# CanBusFinalICSP.net
KiCad netlist of a schematic drawn in EAGLE
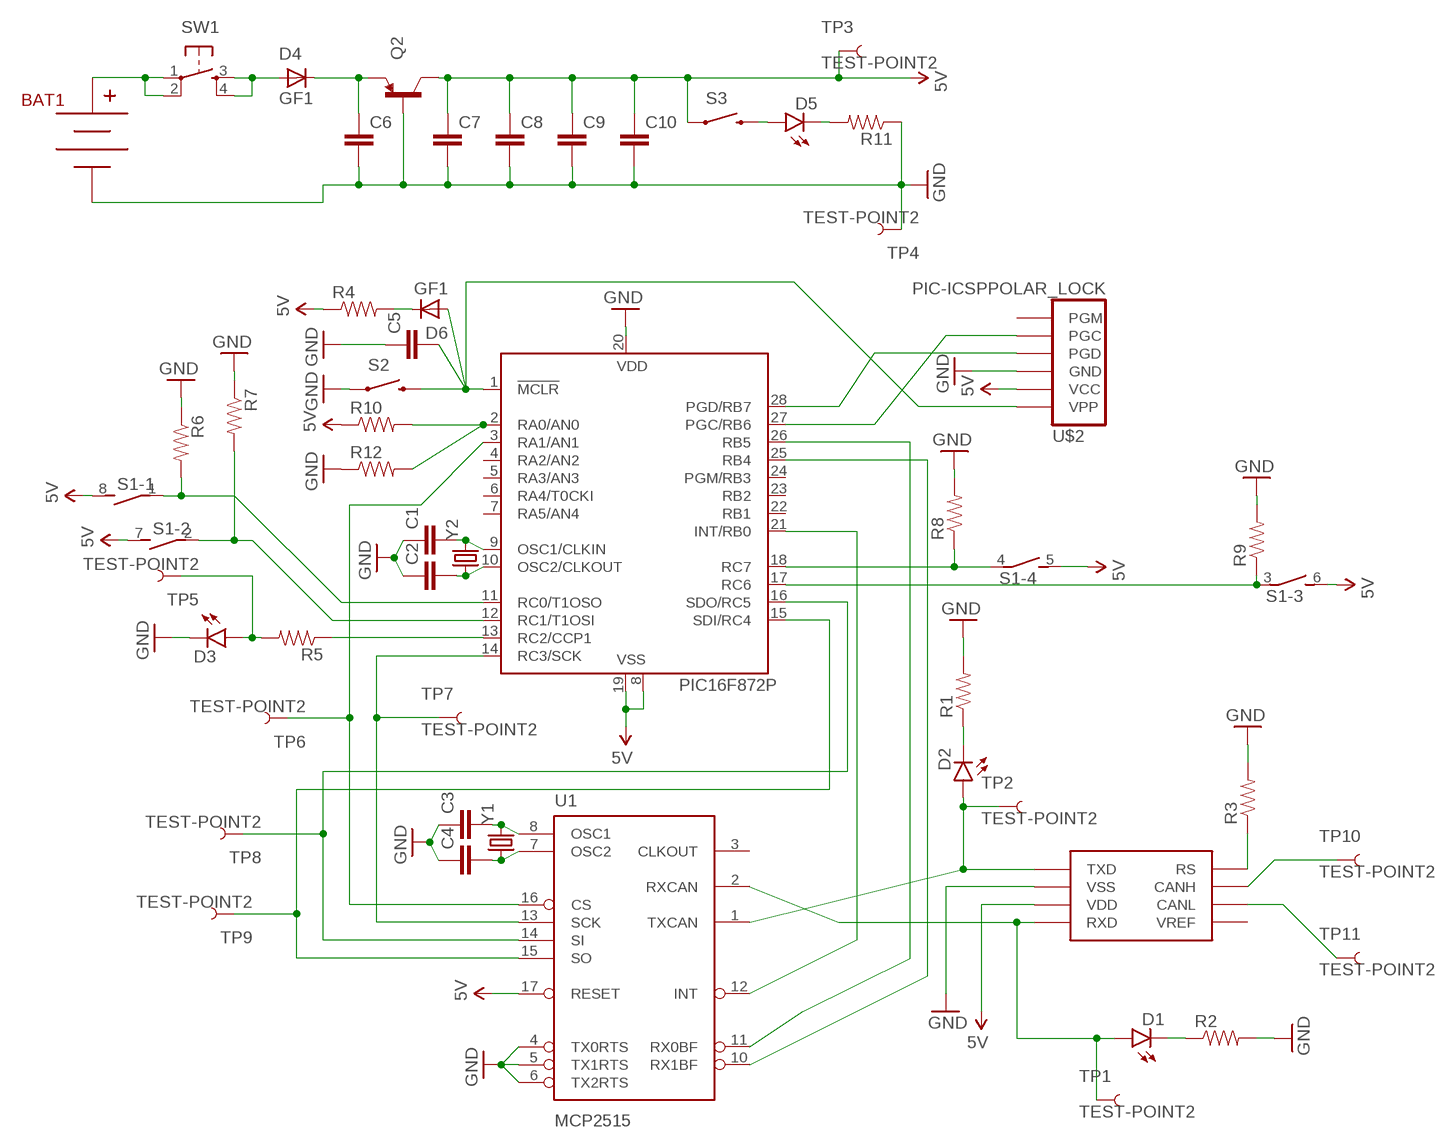
[diagram p0: schematic, sheet 1]

(export (version "E")
  (design (tool "Eeschema 10.0.6"))
  (components
    (comp (ref "BAT1")
      (value "BC9VPC")
      (footprint "eagle-import:BC9VPC")
      (libsource (lib "eagle-import") (part "BC9VPC"))
    )
    (comp (ref "C1")
      (value "CAPPTH")
      (footprint "eagle-import:CAP-PTH-SMALL")
      (libsource (lib "eagle-import") (part "CAPPTH"))
    )
    (comp (ref "C2")
      (value "CAPPTH")
      (footprint "eagle-import:CAP-PTH-SMALL")
      (libsource (lib "eagle-import") (part "CAPPTH"))
    )
    (comp (ref "C3")
      (value "CAPPTH")
      (footprint "eagle-import:CAP-PTH-SMALL")
      (libsource (lib "eagle-import") (part "CAPPTH"))
    )
    (comp (ref "C4")
      (value "CAPPTH")
      (footprint "eagle-import:CAP-PTH-SMALL")
      (libsource (lib "eagle-import") (part "CAPPTH"))
    )
    (comp (ref "C5")
      (value "CAPPTH")
      (footprint "eagle-import:CAP-PTH-SMALL")
      (libsource (lib "eagle-import") (part "CAPPTH"))
    )
    (comp (ref "C6")
      (value "CAPPTH")
      (footprint "eagle-import:CAP-PTH-SMALL")
      (libsource (lib "eagle-import") (part "CAPPTH"))
    )
    (comp (ref "C7")
      (value "CAPPTH")
      (footprint "eagle-import:CAP-PTH-SMALL")
      (libsource (lib "eagle-import") (part "CAPPTH"))
    )
    (comp (ref "C8")
      (value "CAPPTH")
      (footprint "eagle-import:CAP-PTH-SMALL")
      (libsource (lib "eagle-import") (part "CAPPTH"))
    )
    (comp (ref "C9")
      (value "CAPPTH")
      (footprint "eagle-import:CAP-PTH-SMALL")
      (libsource (lib "eagle-import") (part "CAPPTH"))
    )
    (comp (ref "C10")
      (value "CAPPTH")
      (footprint "eagle-import:CAP-PTH-SMALL")
      (libsource (lib "eagle-import") (part "CAPPTH"))
    )
    (comp (ref "D1")
      (value "LED5MM")
      (footprint "eagle-import:LED5MM")
      (libsource (lib "eagle-import") (part "LED5MM"))
    )
    (comp (ref "D2")
      (value "LED5MM")
      (footprint "eagle-import:LED5MM")
      (libsource (lib "eagle-import") (part "LED5MM"))
    )
    (comp (ref "D3")
      (value "LED5MM")
      (footprint "eagle-import:LED5MM")
      (libsource (lib "eagle-import") (part "LED5MM"))
    )
    (comp (ref "D4")
      (value "GF1")
      (footprint "eagle-import:SMA-DO214AC")
      (libsource (lib "eagle-import") (part "GF1"))
    )
    (comp (ref "D5")
      (value "LED5MM")
      (footprint "eagle-import:LED5MM")
      (libsource (lib "eagle-import") (part "LED5MM"))
    )
    (comp (ref "D6")
      (value "GF1")
      (footprint "eagle-import:SMA-DO214AC")
      (libsource (lib "eagle-import") (part "GF1"))
    )
    (comp (ref "IC1")
      (value "PIC16F872P")
      (footprint "eagle-import:DIL28-3")
      (fields (field (name "MF") "MICROCHIP") (field (name "MPN") "PIC16F872-I/SP"))
      (libsource (lib "eagle-import") (part "PIC16872PF"))
    )
    (comp (ref "Q2")
      (value "TRANSISTOR_PNPTO92")
      (footprint "eagle-import:TO-92")
      (libsource (lib "eagle-import") (part "TRANSISTOR_PNPTO92"))
    )
    (comp (ref "R1")
      (value "RESISTOREZ")
      (footprint "eagle-import:AXIAL-0.3EZ")
      (libsource (lib "eagle-import") (part "RESISTOREZ"))
    )
    (comp (ref "R2")
      (value "RESISTOREZ")
      (footprint "eagle-import:AXIAL-0.3EZ")
      (libsource (lib "eagle-import") (part "RESISTOREZ"))
    )
    (comp (ref "R3")
      (value "RESISTOREZ")
      (footprint "eagle-import:AXIAL-0.3EZ")
      (libsource (lib "eagle-import") (part "RESISTOREZ"))
    )
    (comp (ref "R4")
      (value "RESISTOREZ")
      (footprint "eagle-import:AXIAL-0.3EZ")
      (libsource (lib "eagle-import") (part "RESISTOREZ"))
    )
    (comp (ref "R5")
      (value "RESISTOREZ")
      (footprint "eagle-import:AXIAL-0.3EZ")
      (libsource (lib "eagle-import") (part "RESISTOREZ"))
    )
    (comp (ref "R6")
      (value "RESISTOREZ")
      (footprint "eagle-import:AXIAL-0.3EZ")
      (libsource (lib "eagle-import") (part "RESISTOREZ"))
    )
    (comp (ref "R7")
      (value "RESISTOREZ")
      (footprint "eagle-import:AXIAL-0.3EZ")
      (libsource (lib "eagle-import") (part "RESISTOREZ"))
    )
    (comp (ref "R8")
      (value "RESISTOREZ")
      (footprint "eagle-import:AXIAL-0.3EZ")
      (libsource (lib "eagle-import") (part "RESISTOREZ"))
    )
    (comp (ref "R9")
      (value "RESISTOREZ")
      (footprint "eagle-import:AXIAL-0.3EZ")
      (libsource (lib "eagle-import") (part "RESISTOREZ"))
    )
    (comp (ref "R10")
      (value "RESISTOREZ")
      (footprint "eagle-import:AXIAL-0.3EZ")
      (libsource (lib "eagle-import") (part "RESISTOREZ"))
    )
    (comp (ref "R11")
      (value "RESISTOREZ")
      (footprint "eagle-import:AXIAL-0.3EZ")
      (libsource (lib "eagle-import") (part "RESISTOREZ"))
    )
    (comp (ref "R12")
      (value "RESISTORAXIAL-0.3")
      (footprint "eagle-import:AXIAL-0.3")
      (libsource (lib "eagle-import") (part "SparkFun-Resistors_RESISTORAXIAL-0.3"))
    )
    (comp (ref "S1")
      (value "DIP04S")
      (footprint "eagle-import:DIP04S")
      (libsource (lib "eagle-import") (part "DIP04S"))
    )
    (comp (ref "S2")
      (value "SWITCH-MOMENTARY-2PTH")
      (footprint "eagle-import:TACTILE-PTH")
      (libsource (lib "eagle-import") (part "SWITCH-MOMENTARY-2PTH"))
    )
    (comp (ref "S3")
      (value "SWITCH-MOMENTARY-2PTH")
      (footprint "eagle-import:TACTILE-PTH")
      (libsource (lib "eagle-import") (part "SWITCH-MOMENTARY-2PTH"))
    )
    (comp (ref "SW1")
      (value "SWITCH_SPST_4_PINSQUARE")
      (footprint "eagle-import:TACTILE-SWITCH-SMD")
      (libsource (lib "eagle-import") (part "SWITCH_SPST_4_PINSQUARE"))
    )
    (comp (ref "TP1")
      (value "TEST-POINT2")
      (footprint "eagle-import:PAD.02X.02")
      (libsource (lib "eagle-import") (part "TEST-POINT2"))
    )
    (comp (ref "TP2")
      (value "TEST-POINT2")
      (footprint "eagle-import:PAD.02X.02")
      (libsource (lib "eagle-import") (part "TEST-POINT2"))
    )
    (comp (ref "TP3")
      (value "TEST-POINT2")
      (footprint "eagle-import:PAD.02X.02")
      (libsource (lib "eagle-import") (part "TEST-POINT2"))
    )
    (comp (ref "TP4")
      (value "TEST-POINT2")
      (footprint "eagle-import:PAD.02X.02")
      (libsource (lib "eagle-import") (part "TEST-POINT2"))
    )
    (comp (ref "TP5")
      (value "TEST-POINT2")
      (footprint "eagle-import:PAD.02X.02")
      (libsource (lib "eagle-import") (part "TEST-POINT2"))
    )
    (comp (ref "TP6")
      (value "TEST-POINT2")
      (footprint "eagle-import:PAD.02X.02")
      (libsource (lib "eagle-import") (part "TEST-POINT2"))
    )
    (comp (ref "TP7")
      (value "TEST-POINT2")
      (footprint "eagle-import:PAD.02X.02")
      (libsource (lib "eagle-import") (part "TEST-POINT2"))
    )
    (comp (ref "TP8")
      (value "TEST-POINT2")
      (footprint "eagle-import:PAD.02X.02")
      (libsource (lib "eagle-import") (part "TEST-POINT2"))
    )
    (comp (ref "TP9")
      (value "TEST-POINT2")
      (footprint "eagle-import:PAD.02X.02")
      (libsource (lib "eagle-import") (part "TEST-POINT2"))
    )
    (comp (ref "TP10")
      (value "TEST-POINT2")
      (footprint "eagle-import:PAD.02X.02")
      (libsource (lib "eagle-import") (part "TEST-POINT2"))
    )
    (comp (ref "TP11")
      (value "TEST-POINT2")
      (footprint "eagle-import:PAD.02X.02")
      (libsource (lib "eagle-import") (part "TEST-POINT2"))
    )
    (comp (ref "U$1")
      (value "MCP2551")
      (footprint "eagle-import:MCP2551")
      (libsource (lib "eagle-import") (part "MCP2551"))
    )
    (comp (ref "U$2")
      (value "PIC-ICSPPOLAR_LOCK")
      (footprint "eagle-import:MOLEX-1X6_LOCK")
      (libsource (lib "eagle-import") (part "PIC-ICSPPOLAR_LOCK"))
    )
    (comp (ref "U1")
      (value "MCP2515")
      (footprint "eagle-import:DIL18")
      (libsource (lib "eagle-import") (part "MCP2510P"))
    )
    (comp (ref "Y1")
      (value "CRYSTALHC49UV")
      (footprint "eagle-import:HC49U-V")
      (libsource (lib "eagle-import") (part "CRYSTALHC49UV"))
    )
    (comp (ref "Y2")
      (value "CRYSTALHC49UV")
      (footprint "eagle-import:HC49U-V")
      (libsource (lib "eagle-import") (part "CRYSTALHC49UV"))
    )
  )
  (nets
    (net (code "1") (name "5V") (class "Default")
      (node (ref "C10") (pin "1") (pinfunction "1_1") (pintype "passive"))
      (node (ref "C7") (pin "1") (pinfunction "1_1") (pintype "passive"))
      (node (ref "C8") (pin "1") (pinfunction "1_1") (pintype "passive"))
      (node (ref "C9") (pin "1") (pinfunction "1_1") (pintype "passive"))
      (node (ref "IC1") (pin "19") (pinfunction "VSS_19") (pintype "power_in"))
      (node (ref "IC1") (pin "8") (pinfunction "VSS_8") (pintype "power_in"))
      (node (ref "Q2") (pin "3") (pinfunction "C_3") (pintype "passive"))
      (node (ref "R10") (pin "P$1") (pinfunction "1_P$1") (pintype "passive"))
      (node (ref "R4") (pin "P$1") (pinfunction "1_P$1") (pintype "passive"))
      (node (ref "S1") (pin "5") (pinfunction "2_5") (pintype "passive"))
      (node (ref "S1") (pin "6") (pinfunction "2_6") (pintype "passive"))
      (node (ref "S1") (pin "7") (pinfunction "2_7") (pintype "passive"))
      (node (ref "S1") (pin "8") (pinfunction "2_8") (pintype "passive"))
      (node (ref "S3") (pin "1") (pinfunction "1_1") (pintype "passive"))
      (node (ref "TP3") (pin "P$1") (pinfunction "1_P$1") (pintype "bidirectional"))
      (node (ref "U$1") (pin "VDD") (pinfunction "VDD_VDD") (pintype "bidirectional"))
      (node (ref "U$2") (pin "5") (pinfunction "VCC_5") (pintype "bidirectional"))
      (node (ref "U1") (pin "17") (pinfunction "RESET_17") (pintype "input"))
    )
    (net (code "2") (name "GND") (class "Default")
      (node (ref "BAT1") (pin "V-") (pinfunction "V-_V-") (pintype "bidirectional"))
      (node (ref "C1") (pin "1") (pinfunction "1_1") (pintype "passive"))
      (node (ref "C10") (pin "2") (pinfunction "2_2") (pintype "passive"))
      (node (ref "C2") (pin "1") (pinfunction "1_1") (pintype "passive"))
      (node (ref "C3") (pin "1") (pinfunction "1_1") (pintype "passive"))
      (node (ref "C4") (pin "1") (pinfunction "1_1") (pintype "passive"))
      (node (ref "C5") (pin "1") (pinfunction "1_1") (pintype "passive"))
      (node (ref "C6") (pin "2") (pinfunction "2_2") (pintype "passive"))
      (node (ref "C7") (pin "2") (pinfunction "2_2") (pintype "passive"))
      (node (ref "C8") (pin "2") (pinfunction "2_2") (pintype "passive"))
      (node (ref "C9") (pin "2") (pinfunction "2_2") (pintype "passive"))
      (node (ref "D3") (pin "K") (pinfunction "C_K") (pintype "passive"))
      (node (ref "IC1") (pin "20") (pinfunction "VDD_20") (pintype "power_in"))
      (node (ref "Q2") (pin "2") (pinfunction "B_2") (pintype "passive"))
      (node (ref "R1") (pin "P$2") (pinfunction "2_P$2") (pintype "passive"))
      (node (ref "R11") (pin "P$1") (pinfunction "1_P$1") (pintype "passive"))
      (node (ref "R12") (pin "P$1") (pinfunction "1_P$1") (pintype "passive"))
      (node (ref "R2") (pin "P$2") (pinfunction "2_P$2") (pintype "passive"))
      (node (ref "R3") (pin "P$2") (pinfunction "2_P$2") (pintype "passive"))
      (node (ref "R6") (pin "P$1") (pinfunction "1_P$1") (pintype "passive"))
      (node (ref "R7") (pin "P$1") (pinfunction "1_P$1") (pintype "passive"))
      (node (ref "R8") (pin "P$2") (pinfunction "2_P$2") (pintype "passive"))
      (node (ref "R9") (pin "P$2") (pinfunction "2_P$2") (pintype "passive"))
      (node (ref "S2") (pin "1") (pinfunction "1_1") (pintype "passive"))
      (node (ref "TP4") (pin "P$1") (pinfunction "1_P$1") (pintype "bidirectional"))
      (node (ref "U$1") (pin "VSS") (pinfunction "VSS_VSS") (pintype "bidirectional"))
      (node (ref "U$2") (pin "4") (pinfunction "GND_4") (pintype "bidirectional"))
      (node (ref "U1") (pin "4") (pinfunction "TX0RTS_4") (pintype "input"))
      (node (ref "U1") (pin "5") (pinfunction "TX1RTS_5") (pintype "input"))
      (node (ref "U1") (pin "6") (pinfunction "TX2RTS_6") (pintype "input"))
    )
    (net (code "3") (name "Net-(BAT1-PadV+)") (class "Default")
      (node (ref "BAT1") (pin "V+") (pinfunction "V+_V+") (pintype "bidirectional"))
      (node (ref "SW1") (pin "1") (pinfunction "1_1") (pintype "passive"))
      (node (ref "SW1") (pin "2") (pinfunction "2_2") (pintype "passive"))
    )
    (net (code "4") (name "Net-(D1-C)") (class "Default")
      (node (ref "D1") (pin "K") (pinfunction "C_K") (pintype "passive"))
      (node (ref "R2") (pin "P$1") (pinfunction "1_P$1") (pintype "passive"))
    )
    (net (code "5") (name "Net-(D2-C)") (class "Default")
      (node (ref "D2") (pin "K") (pinfunction "C_K") (pintype "passive"))
      (node (ref "R1") (pin "P$1") (pinfunction "1_P$1") (pintype "passive"))
    )
    (net (code "6") (name "Net-(D4-C)") (class "Default")
      (node (ref "C6") (pin "1") (pinfunction "1_1") (pintype "passive"))
      (node (ref "D4") (pin "K") (pinfunction "C_K") (pintype "passive"))
      (node (ref "Q2") (pin "1") (pinfunction "E_1") (pintype "passive"))
    )
    (net (code "7") (name "Net-(D4-PadA)") (class "Default")
      (node (ref "D4") (pin "A") (pinfunction "A_A") (pintype "passive"))
      (node (ref "SW1") (pin "3") (pinfunction "3_3") (pintype "passive"))
      (node (ref "SW1") (pin "4") (pinfunction "4_4") (pintype "passive"))
    )
    (net (code "8") (name "Net-(D5-C)") (class "Default")
      (node (ref "D5") (pin "K") (pinfunction "C_K") (pintype "passive"))
      (node (ref "R11") (pin "P$2") (pinfunction "2_P$2") (pintype "passive"))
    )
    (net (code "9") (name "Net-(D6-C)") (class "Default")
      (node (ref "D6") (pin "K") (pinfunction "C_K") (pintype "passive"))
      (node (ref "R4") (pin "P$2") (pinfunction "2_P$2") (pintype "passive"))
    )
    (net (code "10") (name "Net-(IC1-INT{slash}RB0)") (class "Default")
      (node (ref "IC1") (pin "21") (pinfunction "INT/RB0_21") (pintype "bidirectional"))
      (node (ref "U1") (pin "12") (pinfunction "INT_12") (pintype "output"))
    )
    (net (code "11") (name "Net-(IC1-OSC1{slash}CLKIN)") (class "Default")
      (node (ref "C1") (pin "2") (pinfunction "2_2") (pintype "passive"))
      (node (ref "IC1") (pin "9") (pinfunction "OSC1/CLKIN_9") (pintype "input"))
      (node (ref "Y2") (pin "2") (pinfunction "2_2") (pintype "passive"))
    )
    (net (code "12") (name "Net-(IC1-OSC2{slash}CLKOUT)") (class "Default")
      (node (ref "C2") (pin "2") (pinfunction "2_2") (pintype "passive"))
      (node (ref "IC1") (pin "10") (pinfunction "OSC2/CLKOUT_10") (pintype "output"))
      (node (ref "Y2") (pin "1") (pinfunction "1_1") (pintype "passive"))
    )
    (net (code "13") (name "Net-(IC1-PGC{slash}RB6)") (class "Default")
      (node (ref "IC1") (pin "27") (pinfunction "PGC/RB6_27") (pintype "bidirectional"))
      (node (ref "U$2") (pin "2") (pinfunction "PGC_2") (pintype "bidirectional"))
    )
    (net (code "14") (name "Net-(IC1-PGD{slash}RB7)") (class "Default")
      (node (ref "IC1") (pin "28") (pinfunction "PGD/RB7_28") (pintype "bidirectional"))
      (node (ref "U$2") (pin "3") (pinfunction "PGD_3") (pintype "bidirectional"))
    )
    (net (code "15") (name "Net-(IC1-RA0{slash}AN0)") (class "Default")
      (node (ref "IC1") (pin "2") (pinfunction "RA0/AN0_2") (pintype "bidirectional"))
      (node (ref "R10") (pin "P$2") (pinfunction "2_P$2") (pintype "passive"))
      (node (ref "R12") (pin "P$2") (pinfunction "2_P$2") (pintype "passive"))
    )
    (net (code "16") (name "Net-(IC1-RA1{slash}AN1)") (class "Default")
      (node (ref "IC1") (pin "3") (pinfunction "RA1/AN1_3") (pintype "bidirectional"))
      (node (ref "TP6") (pin "P$1") (pinfunction "1_P$1") (pintype "bidirectional"))
      (node (ref "U1") (pin "16") (pinfunction "CS_16") (pintype "input"))
    )
    (net (code "17") (name "Net-(IC1-RB4)") (class "Default")
      (node (ref "IC1") (pin "25") (pinfunction "RB4_25") (pintype "bidirectional"))
      (node (ref "U1") (pin "10") (pinfunction "RX1BF_10") (pintype "output"))
    )
    (net (code "18") (name "Net-(IC1-RB5)") (class "Default")
      (node (ref "IC1") (pin "26") (pinfunction "RB5_26") (pintype "bidirectional"))
      (node (ref "U1") (pin "11") (pinfunction "RX0BF_11") (pintype "output"))
    )
    (net (code "19") (name "Net-(IC1-RC0{slash}T1OSO)") (class "Default")
      (node (ref "IC1") (pin "11") (pinfunction "RC0/T1OSO_11") (pintype "bidirectional"))
      (node (ref "R6") (pin "P$2") (pinfunction "2_P$2") (pintype "passive"))
      (node (ref "S1") (pin "1") (pinfunction "1_1") (pintype "passive"))
    )
    (net (code "20") (name "Net-(IC1-RC1{slash}T1OSI)") (class "Default")
      (node (ref "IC1") (pin "12") (pinfunction "RC1/T1OSI_12") (pintype "bidirectional"))
      (node (ref "R7") (pin "P$2") (pinfunction "2_P$2") (pintype "passive"))
      (node (ref "S1") (pin "2") (pinfunction "1_2") (pintype "passive"))
    )
    (net (code "21") (name "Net-(IC1-RC2{slash}CCP1)") (class "Default")
      (node (ref "IC1") (pin "13") (pinfunction "RC2/CCP1_13") (pintype "bidirectional"))
      (node (ref "R5") (pin "P$1") (pinfunction "1_P$1") (pintype "passive"))
    )
    (net (code "22") (name "Net-(IC1-RC3{slash}SCK)") (class "Default")
      (node (ref "IC1") (pin "14") (pinfunction "RC3/SCK_14") (pintype "bidirectional"))
      (node (ref "TP7") (pin "P$1") (pinfunction "1_P$1") (pintype "bidirectional"))
      (node (ref "U1") (pin "13") (pinfunction "SCK_13") (pintype "input"))
    )
    (net (code "23") (name "Net-(IC1-RC6)") (class "Default")
      (node (ref "IC1") (pin "17") (pinfunction "RC6_17") (pintype "bidirectional"))
      (node (ref "R9") (pin "P$1") (pinfunction "1_P$1") (pintype "passive"))
      (node (ref "S1") (pin "3") (pinfunction "1_3") (pintype "passive"))
    )
    (net (code "24") (name "Net-(IC1-RC7)") (class "Default")
      (node (ref "IC1") (pin "18") (pinfunction "RC7_18") (pintype "bidirectional"))
      (node (ref "R8") (pin "P$1") (pinfunction "1_P$1") (pintype "passive"))
      (node (ref "S1") (pin "4") (pinfunction "1_4") (pintype "passive"))
    )
    (net (code "25") (name "Net-(IC1-SDI{slash}RC4)") (class "Default")
      (node (ref "IC1") (pin "15") (pinfunction "SDI/RC4_15") (pintype "bidirectional"))
      (node (ref "TP9") (pin "P$1") (pinfunction "1_P$1") (pintype "bidirectional"))
      (node (ref "U1") (pin "15") (pinfunction "SO_15") (pintype "output"))
    )
    (net (code "26") (name "Net-(IC1-SDO{slash}RC5)") (class "Default")
      (node (ref "IC1") (pin "16") (pinfunction "SDO/RC5_16") (pintype "bidirectional"))
      (node (ref "TP8") (pin "P$1") (pinfunction "1_P$1") (pintype "bidirectional"))
      (node (ref "U1") (pin "14") (pinfunction "SI_14") (pintype "input"))
    )
    (net (code "27") (name "Net-(IC1-~{MCLR})") (class "Default")
      (node (ref "C5") (pin "2") (pinfunction "2_2") (pintype "passive"))
      (node (ref "D6") (pin "A") (pinfunction "A_A") (pintype "passive"))
      (node (ref "IC1") (pin "1") (pinfunction "~{MCLR}_1") (pintype "input"))
      (node (ref "S2") (pin "3") (pinfunction "2_3") (pintype "passive"))
      (node (ref "U$2") (pin "6") (pinfunction "VPP_6") (pintype "bidirectional"))
    )
    (net (code "28") (name "Net-(R3-1)") (class "Default")
      (node (ref "R3") (pin "P$1") (pinfunction "1_P$1") (pintype "passive"))
      (node (ref "U$1") (pin "RS") (pinfunction "RS_RS") (pintype "bidirectional"))
    )
    (net (code "29") (name "Net-(R5-2)") (class "Default")
      (node (ref "D3") (pin "A") (pinfunction "A_A") (pintype "passive"))
      (node (ref "R5") (pin "P$2") (pinfunction "2_P$2") (pintype "passive"))
      (node (ref "TP5") (pin "P$1") (pinfunction "1_P$1") (pintype "bidirectional"))
    )
    (net (code "30") (name "Net-(S3-2)") (class "Default")
      (node (ref "D5") (pin "A") (pinfunction "A_A") (pintype "passive"))
      (node (ref "S3") (pin "3") (pinfunction "2_3") (pintype "passive"))
    )
    (net (code "31") (name "Net-(TP1-1)") (class "Default")
      (node (ref "D1") (pin "A") (pinfunction "A_A") (pintype "passive"))
      (node (ref "TP1") (pin "P$1") (pinfunction "1_P$1") (pintype "bidirectional"))
      (node (ref "U$1") (pin "RXD") (pinfunction "RXD_RXD") (pintype "bidirectional"))
      (node (ref "U1") (pin "2") (pinfunction "RXCAN_2") (pintype "input"))
    )
    (net (code "32") (name "Net-(TP2-1)") (class "Default")
      (node (ref "D2") (pin "A") (pinfunction "A_A") (pintype "passive"))
      (node (ref "TP2") (pin "P$1") (pinfunction "1_P$1") (pintype "bidirectional"))
      (node (ref "U$1") (pin "TXD") (pinfunction "TXD_TXD") (pintype "bidirectional"))
      (node (ref "U1") (pin "1") (pinfunction "TXCAN_1") (pintype "output"))
    )
    (net (code "33") (name "Net-(TP10-1)") (class "Default")
      (node (ref "TP10") (pin "P$1") (pinfunction "1_P$1") (pintype "bidirectional"))
      (node (ref "U$1") (pin "CANH") (pinfunction "CANH_CANH") (pintype "bidirectional"))
    )
    (net (code "34") (name "Net-(TP11-1)") (class "Default")
      (node (ref "TP11") (pin "P$1") (pinfunction "1_P$1") (pintype "bidirectional"))
      (node (ref "U$1") (pin "CANL") (pinfunction "CANL_CANL") (pintype "bidirectional"))
    )
    (net (code "35") (name "Net-(U1A-OSC1)") (class "Default")
      (node (ref "C3") (pin "2") (pinfunction "2_2") (pintype "passive"))
      (node (ref "U1") (pin "8") (pinfunction "OSC1_8") (pintype "input"))
      (node (ref "Y1") (pin "2") (pinfunction "2_2") (pintype "passive"))
    )
    (net (code "36") (name "Net-(U1A-OSC2)") (class "Default")
      (node (ref "C4") (pin "2") (pinfunction "2_2") (pintype "passive"))
      (node (ref "U1") (pin "7") (pinfunction "OSC2_7") (pintype "output"))
      (node (ref "Y1") (pin "1") (pinfunction "1_1") (pintype "passive"))
    )
    (net (code "37") (name "unconnected-(IC1-PGM{slash}RB3-Pad24)") (class "Default")
      (node (ref "IC1") (pin "24") (pinfunction "PGM/RB3_24") (pintype "bidirectional"))
    )
    (net (code "38") (name "unconnected-(IC1-RA2{slash}AN2-Pad4)") (class "Default")
      (node (ref "IC1") (pin "4") (pinfunction "RA2/AN2_4") (pintype "bidirectional"))
    )
    (net (code "39") (name "unconnected-(IC1-RA3{slash}AN3-Pad5)") (class "Default")
      (node (ref "IC1") (pin "5") (pinfunction "RA3/AN3_5") (pintype "bidirectional"))
    )
    (net (code "40") (name "unconnected-(IC1-RA4{slash}T0CKI-Pad6)") (class "Default")
      (node (ref "IC1") (pin "6") (pinfunction "RA4/T0CKI_6") (pintype "bidirectional"))
    )
    (net (code "41") (name "unconnected-(IC1-RA5{slash}AN4-Pad7)") (class "Default")
      (node (ref "IC1") (pin "7") (pinfunction "RA5/AN4_7") (pintype "bidirectional"))
    )
    (net (code "42") (name "unconnected-(IC1-RB1-Pad22)") (class "Default")
      (node (ref "IC1") (pin "22") (pinfunction "RB1_22") (pintype "bidirectional"))
    )
    (net (code "43") (name "unconnected-(IC1-RB2-Pad23)") (class "Default")
      (node (ref "IC1") (pin "23") (pinfunction "RB2_23") (pintype "bidirectional"))
    )
    (net (code "44") (name "unconnected-(U$1-PadVREF)") (class "Default")
      (node (ref "U$1") (pin "VREF") (pinfunction "VREF_VREF") (pintype "bidirectional"))
    )
    (net (code "45") (name "unconnected-(U$2-PGM-Pad1)") (class "Default")
      (node (ref "U$2") (pin "1") (pinfunction "PGM_1") (pintype "bidirectional"))
    )
    (net (code "46") (name "unconnected-(U1A-CLKOUT-Pad3)") (class "Default")
      (node (ref "U1") (pin "3") (pinfunction "CLKOUT_3") (pintype "output"))
    )
  )
)
